# laser.net
KiCad netlist of a schematic drawn in Altium Designer
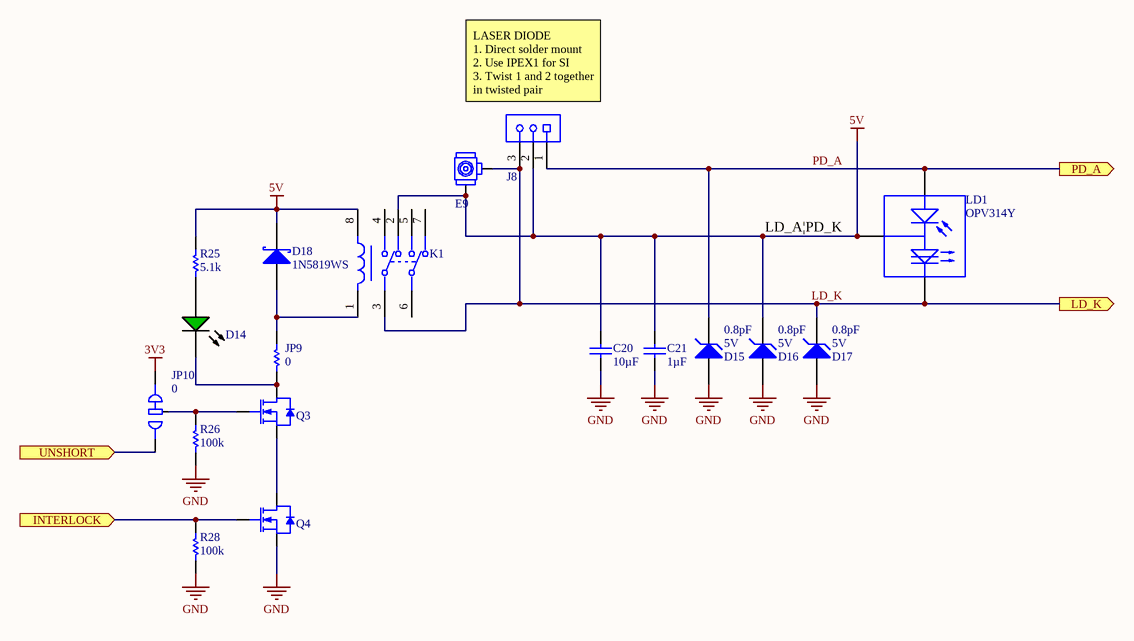
[diagram p0: laser.SchDoc]

(export (version "E")
  (design (tool "Eeschema 10.0.6"))
  (components
    (comp (ref "C20")
      (value "10µF")
      (footprint "CAPC1005X06N")
      (description "Cap Ceramic 10uF 6.3V X5R 20% SMD 0402 85°C Paper T/R")
      (fields (field (name "TOLERANCE") "20%") (field (name "Comment") "CL05A106MQ5NUNC"))
      (libsource (lib "UWA Aerospace") (part "Capacitor - Non-polar"))
    )
    (comp (ref "C21")
      (value "1µF")
      (footprint "CAPC1005X06N")
      (fields (field (name "TOLERANCE") "10%") (field (name "Comment") "CL05A105KA5NQNC"))
      (libsource (lib "UWA Aerospace") (part "Capacitor - Non-polar"))
    )
    (comp (ref "D14")
      (value "KT-0805G")
      (footprint "LED_0805")
      (description "Emerald 0805  Light Emitting Diodes (LED) ROHS green")
      (libsource (lib "UWA Aerospace") (part "LED - Green"))
    )
    (comp (ref "D15")
      (value "5V")
      (footprint "DFN60P100X45-2L")
      (description "5A 55W 16V 9V Unidirectional 5V DFN1006-2L  ESD and Surge Protection (TVS/ESD) ROHS")
      (fields (field (name "CAPACITANCE") "0.8pF") (field (name "Comment") "H5VU10U"))
      (libsource (lib "UWA Aerospace") (part "Diode - Zener"))
    )
    (comp (ref "D16")
      (value "5V")
      (footprint "DFN60P100X45-2L")
      (description "5A 55W 16V 9V Unidirectional 5V DFN1006-2L  ESD and Surge Protection (TVS/ESD) ROHS")
      (fields (field (name "CAPACITANCE") "0.8pF") (field (name "Comment") "H5VU10U"))
      (libsource (lib "UWA Aerospace") (part "Diode - Zener"))
    )
    (comp (ref "D17")
      (value "5V")
      (footprint "DFN60P100X45-2L")
      (description "5A 55W 16V 9V Unidirectional 5V DFN1006-2L  ESD and Surge Protection (TVS/ESD) ROHS")
      (fields (field (name "CAPACITANCE") "0.8pF") (field (name "Comment") "H5VU10U"))
      (libsource (lib "UWA Aerospace") (part "Diode - Zener"))
    )
    (comp (ref "D18")
      (value "1N5819WS")
      (footprint "SODFL250X100-2N")
      (description "VR=40V IF=1A 120pF P=250mW")
      (libsource (lib "UWA Aerospace") (part "Diode - Schottky"))
    )
    (comp (ref "E9")
      (value "U.FL-R-SMT-1(01)")
      (footprint "HRS-U.FL-R-SMT-3_V 4_LAYER_KO")
      (description "Rf Connectors / Coaxial Connectors SMT Ml Rec Au 50 Ohm W/anti Sldr Wicking UFL")
      (fields (field (name "SOURCE") "UWAA_Stock"))
      (libsource (lib "UWA Aerospace") (part "U.FL Connector"))
    )
    (comp (ref "J8")
      (value "B3B-PH-K-S(LF)(SN)")
      (footprint "JST-B3B-PH-K-S-3_V")
      (description "Connector Header, PH Series, 3 Position, 2.00mm, Through Hole, Press-Fit, Solder, Natural")
      (libsource (lib "UWA Aerospace") (part "Connector - 1x3 Single Sided"))
    )
    (comp (ref "JP9")
      (value "0")
      (footprint "RESC1005X04N")
      (description "Metal Glaze/thick Film, 0.0625W, 0ohm, 0402")
      (fields (field (name "TOLERANCE") "1%") (field (name "Comment") "0402WGF0000TCE"))
      (libsource (lib "UWA Aerospace") (part "Resistor"))
    )
    (comp (ref "JP10")
      (value "0")
      (footprint "RESC1005X04N TWO STATE")
      (description "JUMPER-0402 TWO STATE Fixed Resistor, Metal Glaze/thick Film, 0.1W, 0ohm, Surface Mount, 0402")
      (fields (field (name "TOLERANCE") "1%") (field (name "Comment") "JUMPER-0402 TWO STATE"))
      (libsource (lib "UWA Aerospace") (part "Jumper - Two state"))
    )
    (comp (ref "K1")
      (value "AGQ200A4HX")
      (footprint "FP-AGQ200S03Z-MFG")
      (description "Electromechanical Relay 4.5VDC 145Ohm 2A DPDT (10.6x8.4x5.4)mm SMD General Purpose Relay")
      (fields (field (name "SOURCE") "Distributor"))
      (libsource (lib "UWA Aerospace") (part "58c38101009d5ebbf9054263c5b66d6"))
    )
    (comp (ref "LD1")
      (value "OPV314Y")
      (footprint "TO-18")
      (description "VCSEL Emitter, 840nm Min, 860nm Max, 2500Mbps, TO-46, Through Hole Mount")
      (libsource (lib "UWA Aerospace") (part "Laser Diode w/ Monitor Photodiode"))
    )
    (comp (ref "Q3")
      (value "MDD2302")
      (footprint "SOT95P252X140-3N")
      (description "4A 25mΩ@4.5V null SOT-23 MOSFETs ROHS N CHANNEL")
      (libsource (lib "UWA Aerospace") (part "Transistor - MOSFET N-Channel"))
    )
    (comp (ref "Q4")
      (value "MDD2302")
      (footprint "SOT95P252X140-3N")
      (description "4A 25mΩ@4.5V null SOT-23 MOSFETs ROHS N CHANNEL")
      (libsource (lib "UWA Aerospace") (part "Transistor - MOSFET N-Channel"))
    )
    (comp (ref "R25")
      (value "5.1k")
      (footprint "RESC1005X04N")
      (fields (field (name "TOLERANCE") "1%") (field (name "Comment") "0402WGF5101TCE"))
      (libsource (lib "UWA Aerospace") (part "Resistor"))
    )
    (comp (ref "R26")
      (value "100k")
      (footprint "RESC1005X04N")
      (description "RES 100K OHM 1% 1/16W 0402")
      (fields (field (name "TOLERANCE") "1%") (field (name "Comment") "CRCW0402100KFKEDC"))
      (libsource (lib "UWA Aerospace") (part "WSLP1206R0500FEA"))
    )
    (comp (ref "R28")
      (value "100k")
      (footprint "RESC1005X04N")
      (description "RES 100K OHM 1% 1/16W 0402")
      (fields (field (name "TOLERANCE") "1%") (field (name "Comment") "CRCW0402100KFKEDC"))
      (libsource (lib "UWA Aerospace") (part "WSLP1206R0500FEA"))
    )
  )
  (nets
    (net (code "1") (name "/INTERLOCK") (class "Default")
      (node (ref "Q4") (pin "1") (pinfunction "G_1") (pintype "passive"))
      (node (ref "R28") (pin "2") (pinfunction "2_2") (pintype "passive"))
    )
    (net (code "2") (name "/LD_K") (class "Default")
      (node (ref "D17") (pin "1") (pinfunction "K_1") (pintype "passive"))
      (node (ref "E9") (pin "1") (pinfunction "SIG_1") (pintype "passive"))
      (node (ref "J8") (pin "3") (pinfunction "3_3") (pintype "passive"))
      (node (ref "K1") (pin "3") (pinfunction "3_3") (pintype "passive"))
      (node (ref "LD1") (pin "1") (pinfunction "LD_K_1") (pintype "passive"))
    )
    (net (code "3") (name "/PD_A") (class "Default")
      (node (ref "D15") (pin "1") (pinfunction "K_1") (pintype "passive"))
      (node (ref "J8") (pin "1") (pinfunction "1_1") (pintype "passive"))
      (node (ref "LD1") (pin "3") (pinfunction "PD_A_3") (pintype "passive"))
    )
    (net (code "4") (name "/UNSHORT") (class "Default")
      (node (ref "JP10") (pin "1") (pinfunction "1_1") (pintype "passive"))
    )
    (net (code "5") (name "3V3") (class "Default")
      (node (ref "JP10") (pin "2") (pinfunction "2_2") (pintype "passive"))
    )
    (net (code "6") (name "5V") (class "Default")
      (node (ref "C20") (pin "2") (pinfunction "2_2") (pintype "passive"))
      (node (ref "C21") (pin "2") (pinfunction "2_2") (pintype "passive"))
      (node (ref "D16") (pin "1") (pinfunction "K_1") (pintype "passive"))
      (node (ref "D18") (pin "1") (pinfunction "K_1") (pintype "passive"))
      (node (ref "E9") (pin "2") (pinfunction "GND_2") (pintype "passive"))
      (node (ref "J8") (pin "2") (pinfunction "2_2") (pintype "passive"))
      (node (ref "K1") (pin "2") (pinfunction "2_2") (pintype "passive"))
      (node (ref "K1") (pin "8") (pinfunction "8_8") (pintype "passive"))
      (node (ref "LD1") (pin "2") (pinfunction "COM_2") (pintype "passive"))
      (node (ref "R25") (pin "2") (pinfunction "2_2") (pintype "passive"))
    )
    (net (code "7") (name "GND") (class "Default")
      (node (ref "C20") (pin "1") (pinfunction "1_1") (pintype "passive"))
      (node (ref "C21") (pin "1") (pinfunction "1_1") (pintype "passive"))
      (node (ref "D15") (pin "2") (pinfunction "A_2") (pintype "passive"))
      (node (ref "D16") (pin "2") (pinfunction "A_2") (pintype "passive"))
      (node (ref "D17") (pin "2") (pinfunction "A_2") (pintype "passive"))
      (node (ref "Q4") (pin "2") (pinfunction "S_2") (pintype "passive"))
      (node (ref "R26") (pin "1") (pinfunction "1_1") (pintype "passive"))
      (node (ref "R28") (pin "1") (pinfunction "1_1") (pintype "passive"))
    )
    (net (code "8") (name "Net-(D14-A)") (class "Default")
      (node (ref "D14") (pin "2") (pinfunction "A_2") (pintype "passive"))
      (node (ref "R25") (pin "1") (pinfunction "1_1") (pintype "passive"))
    )
    (net (code "9") (name "Net-(D14-K)") (class "Default")
      (node (ref "D14") (pin "1") (pinfunction "K_1") (pintype "passive"))
      (node (ref "JP9") (pin "1") (pinfunction "1_1") (pintype "passive"))
      (node (ref "Q3") (pin "3") (pinfunction "D_3") (pintype "passive"))
    )
    (net (code "10") (name "Net-(D18-A)") (class "Default")
      (node (ref "D18") (pin "2") (pinfunction "A_2") (pintype "passive"))
      (node (ref "JP9") (pin "2") (pinfunction "2_2") (pintype "passive"))
      (node (ref "K1") (pin "1") (pinfunction "1_1") (pintype "passive"))
    )
    (net (code "11") (name "Net-(JP10-COM)") (class "Default")
      (node (ref "JP10") (pin "3") (pinfunction "COM_3") (pintype "passive"))
      (node (ref "Q3") (pin "1") (pinfunction "G_1") (pintype "passive"))
      (node (ref "R26") (pin "2") (pinfunction "2_2") (pintype "passive"))
    )
    (net (code "12") (name "Net-(Q3-S)") (class "Default")
      (node (ref "Q3") (pin "2") (pinfunction "S_2") (pintype "passive"))
      (node (ref "Q4") (pin "3") (pinfunction "D_3") (pintype "passive"))
    )
    (net (code "13") (name "unconnected-(K1-Pad4)") (class "Default")
      (node (ref "K1") (pin "4") (pinfunction "4_4") (pintype "passive"))
    )
    (net (code "14") (name "unconnected-(K1-Pad5)") (class "Default")
      (node (ref "K1") (pin "5") (pinfunction "5_5") (pintype "passive"))
    )
    (net (code "15") (name "unconnected-(K1-Pad6)") (class "Default")
      (node (ref "K1") (pin "6") (pinfunction "6_6") (pintype "passive"))
    )
    (net (code "16") (name "unconnected-(K1-Pad7)") (class "Default")
      (node (ref "K1") (pin "7") (pinfunction "7_7") (pintype "passive"))
    )
  )
)
